# Power_Distro_Board.net
KiCad netlist of a schematic drawn in EAGLE
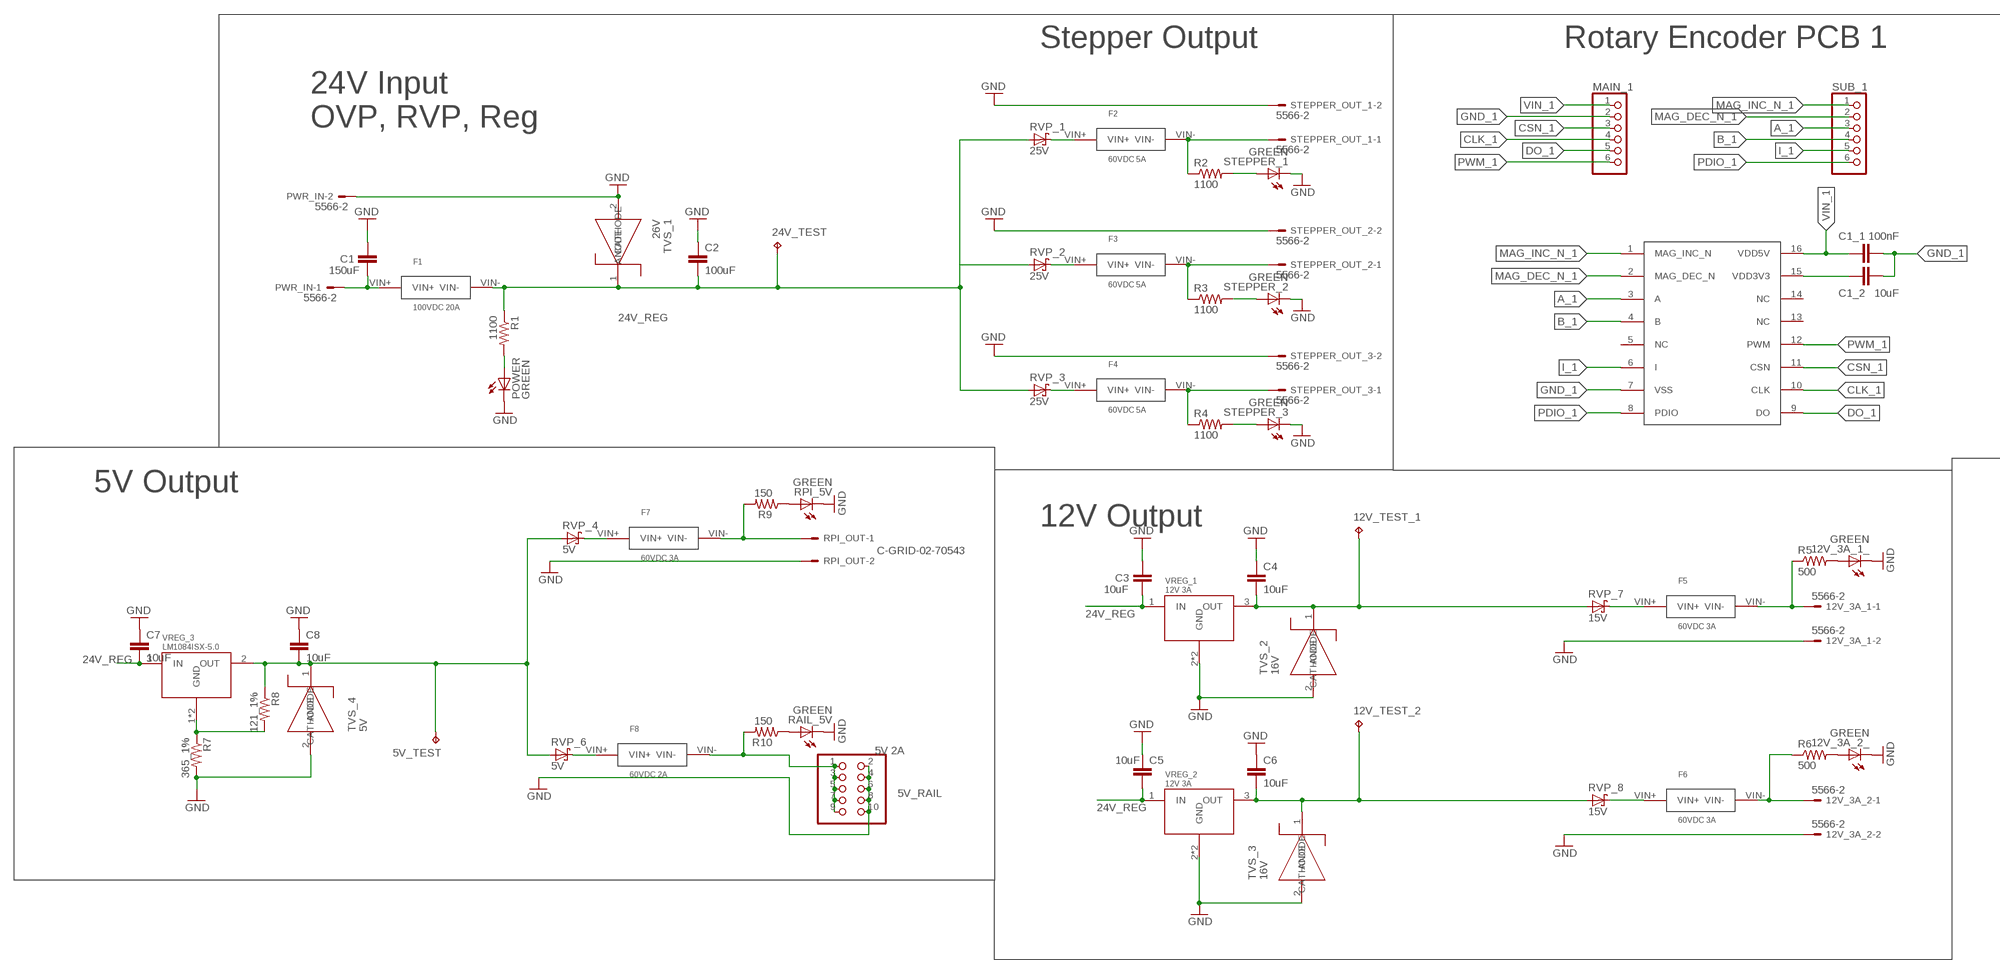
[diagram p0: schematic, sheet 1, part 1 of 2]
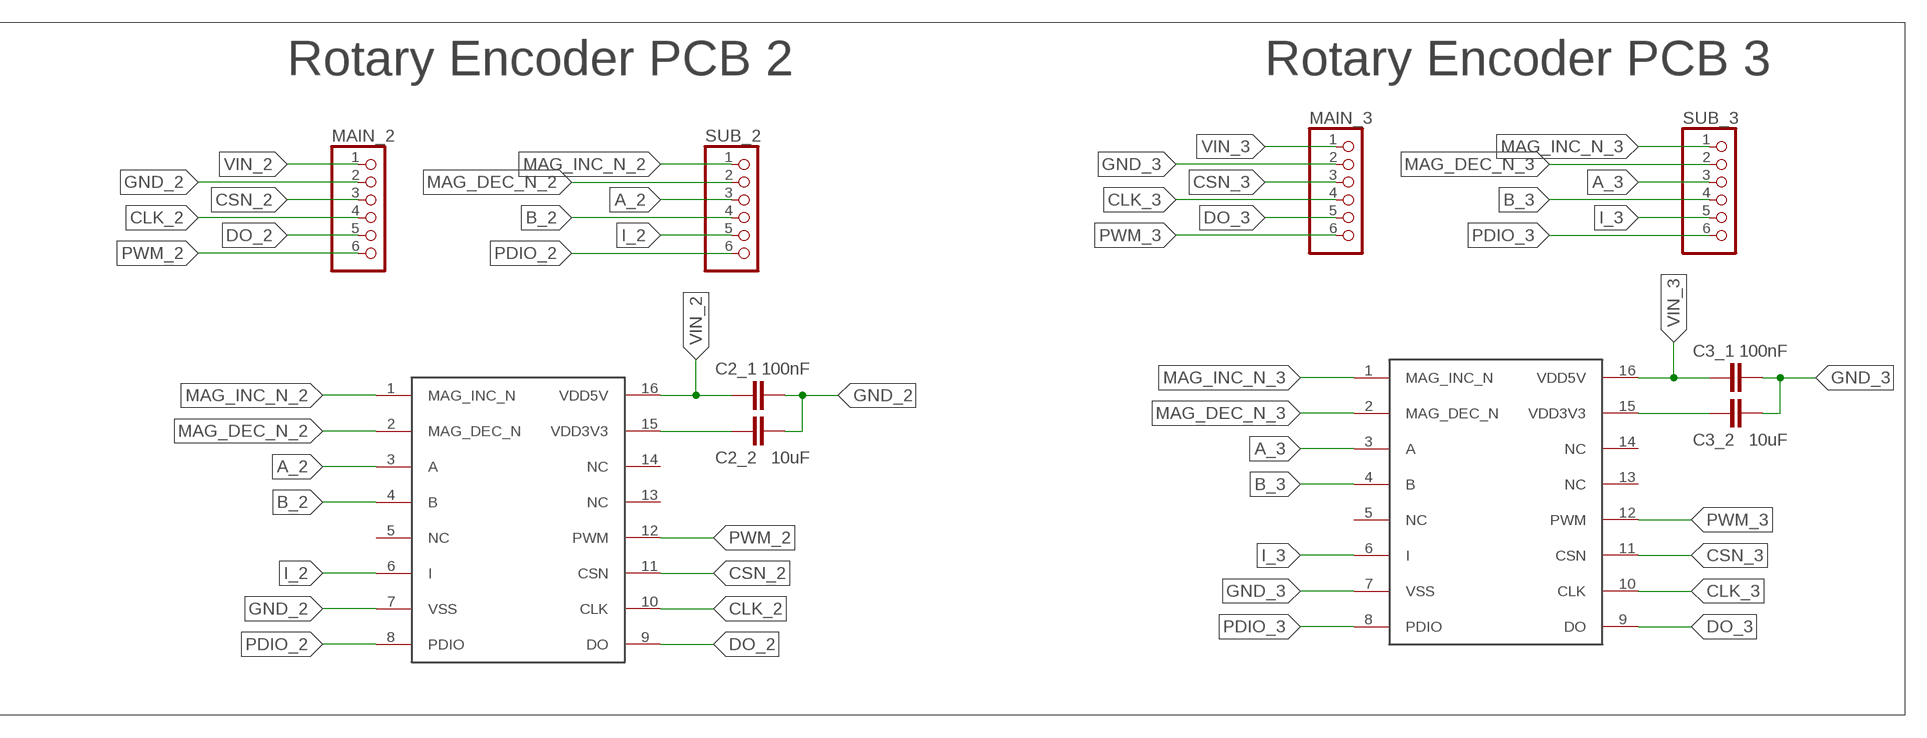
[diagram p1: schematic, sheet 1, part 2 of 2]

(export (version "E")
  (design (tool "Eeschema 10.0.6"))
  (components
    (comp (ref "5V_RAIL")
      (value "5V 2A")
      (footprint "eagle-import:2X05")
      (libsource (lib "eagle-import") (part "PINHD-2X5"))
    )
    (comp (ref "5V_TEST")
      (value "TPPAD1-13")
      (footprint "eagle-import:P1-13")
      (libsource (lib "eagle-import") (part "TPPAD1-13"))
    )
    (comp (ref "12V_3A_1")
      (value "5566-2")
      (footprint "eagle-import:5566-2")
      (libsource (lib "eagle-import") (part "5566-2"))
    )
    (comp (ref "12V_3A_1_")
      (value "GREEN")
      (footprint "eagle-import:SML1206")
      (libsource (lib "eagle-import") (part "LEDSML1206"))
    )
    (comp (ref "12V_3A_2")
      (value "5566-2")
      (footprint "eagle-import:5566-2")
      (libsource (lib "eagle-import") (part "5566-2"))
    )
    (comp (ref "12V_3A_2_")
      (value "GREEN")
      (footprint "eagle-import:SML1206")
      (libsource (lib "eagle-import") (part "LEDSML1206"))
    )
    (comp (ref "12V_TEST_1")
      (value "TPPAD1-13")
      (footprint "eagle-import:P1-13")
      (libsource (lib "eagle-import") (part "TPPAD1-13"))
    )
    (comp (ref "12V_TEST_2")
      (value "TPPAD1-13")
      (footprint "eagle-import:P1-13")
      (libsource (lib "eagle-import") (part "TPPAD1-13"))
    )
    (comp (ref "24V_TEST")
      (value "TPPAD1-13")
      (footprint "eagle-import:P1-13")
      (libsource (lib "eagle-import") (part "TPPAD1-13"))
    )
    (comp (ref "C1")
      (value "150uF")
      (footprint "eagle-import:C1206")
      (libsource (lib "eagle-import") (part "C-EUC1206"))
    )
    (comp (ref "C1_1")
      (value "100nF")
      (footprint "eagle-import:C1206")
      (libsource (lib "eagle-import") (part "C-EUC1206"))
    )
    (comp (ref "C1_2")
      (value "10uF")
      (footprint "eagle-import:C1206")
      (libsource (lib "eagle-import") (part "C-EUC1206"))
    )
    (comp (ref "C2")
      (value "100uF")
      (footprint "eagle-import:C1206")
      (libsource (lib "eagle-import") (part "C-EUC1206"))
    )
    (comp (ref "C2_1")
      (value "100nF")
      (footprint "eagle-import:C1206")
      (libsource (lib "eagle-import") (part "C-EUC1206"))
    )
    (comp (ref "C2_2")
      (value "10uF")
      (footprint "eagle-import:C1206")
      (libsource (lib "eagle-import") (part "C-EUC1206"))
    )
    (comp (ref "C3")
      (value "10uF")
      (footprint "eagle-import:C1206")
      (libsource (lib "eagle-import") (part "C-EUC1206"))
    )
    (comp (ref "C3_1")
      (value "100nF")
      (footprint "eagle-import:C1206")
      (libsource (lib "eagle-import") (part "C-EUC1206"))
    )
    (comp (ref "C3_2")
      (value "10uF")
      (footprint "eagle-import:C1206")
      (libsource (lib "eagle-import") (part "C-EUC1206"))
    )
    (comp (ref "C4")
      (value "10uF")
      (footprint "eagle-import:C1206")
      (libsource (lib "eagle-import") (part "C-EUC1206"))
    )
    (comp (ref "C5")
      (value "10uF")
      (footprint "eagle-import:C1206")
      (libsource (lib "eagle-import") (part "C-EUC1206"))
    )
    (comp (ref "C6")
      (value "10uF")
      (footprint "eagle-import:C1206")
      (libsource (lib "eagle-import") (part "C-EUC1206"))
    )
    (comp (ref "C7")
      (value "10uF")
      (footprint "eagle-import:C1206")
      (libsource (lib "eagle-import") (part "C-EUC1206"))
    )
    (comp (ref "C8")
      (value "10uF")
      (footprint "eagle-import:C1206")
      (libsource (lib "eagle-import") (part "C-EUC1206"))
    )
    (comp (ref "ENC_1")
      (value "ENCODER_AS5045B")
      (footprint "eagle-import:SSOP16")
      (libsource (lib "eagle-import") (part "ENCODER_AS5045B"))
    )
    (comp (ref "ENC_2")
      (value "ENCODER_AS5045B")
      (footprint "eagle-import:SSOP16")
      (libsource (lib "eagle-import") (part "ENCODER_AS5045B"))
    )
    (comp (ref "ENC_3")
      (value "ENCODER_AS5045B")
      (footprint "eagle-import:SSOP16")
      (libsource (lib "eagle-import") (part "ENCODER_AS5045B"))
    )
    (comp (ref "F1")
      (value "100VDC 20A")
      (footprint "eagle-import:NANO")
      (libsource (lib "eagle-import") (part "LITTLEFUSENANO463"))
    )
    (comp (ref "F2")
      (value "60VDC 5A")
      (footprint "eagle-import:OMNI_BLOCK")
      (libsource (lib "eagle-import") (part "LITTLEFUSE0154"))
    )
    (comp (ref "F3")
      (value "60VDC 5A")
      (footprint "eagle-import:OMNI_BLOCK")
      (libsource (lib "eagle-import") (part "LITTLEFUSE0154"))
    )
    (comp (ref "F4")
      (value "60VDC 5A")
      (footprint "eagle-import:OMNI_BLOCK")
      (libsource (lib "eagle-import") (part "LITTLEFUSE0154"))
    )
    (comp (ref "F5")
      (value "60VDC 3A")
      (footprint "eagle-import:OMNI_BLOCK")
      (libsource (lib "eagle-import") (part "LITTLEFUSE0154"))
    )
    (comp (ref "F6")
      (value "60VDC 3A")
      (footprint "eagle-import:OMNI_BLOCK")
      (libsource (lib "eagle-import") (part "LITTLEFUSE0154"))
    )
    (comp (ref "F7")
      (value "60VDC 3A")
      (footprint "eagle-import:OMNI_BLOCK")
      (libsource (lib "eagle-import") (part "LITTLEFUSE0154"))
    )
    (comp (ref "F8")
      (value "60VDC 2A")
      (footprint "eagle-import:OMNI_BLOCK")
      (libsource (lib "eagle-import") (part "LITTLEFUSE0154"))
    )
    (comp (ref "MAIN_1")
      (value "PINHD-1X6")
      (footprint "eagle-import:1X06")
      (libsource (lib "eagle-import") (part "PINHD-1X6"))
    )
    (comp (ref "MAIN_2")
      (value "PINHD-1X6")
      (footprint "eagle-import:1X06")
      (libsource (lib "eagle-import") (part "PINHD-1X6"))
    )
    (comp (ref "MAIN_3")
      (value "PINHD-1X6")
      (footprint "eagle-import:1X06")
      (libsource (lib "eagle-import") (part "PINHD-1X6"))
    )
    (comp (ref "POWER")
      (value "GREEN")
      (footprint "eagle-import:SML1206")
      (libsource (lib "eagle-import") (part "LEDSML1206"))
    )
    (comp (ref "PWR_IN")
      (value "5566-2")
      (footprint "eagle-import:5566-2")
      (libsource (lib "eagle-import") (part "5566-2"))
    )
    (comp (ref "R1")
      (value "1100")
      (footprint "eagle-import:R1206")
      (libsource (lib "eagle-import") (part "R-US_R1206"))
    )
    (comp (ref "R2")
      (value "1100")
      (footprint "eagle-import:R1206")
      (libsource (lib "eagle-import") (part "R-US_R1206"))
    )
    (comp (ref "R3")
      (value "1100")
      (footprint "eagle-import:R1206")
      (libsource (lib "eagle-import") (part "R-US_R1206"))
    )
    (comp (ref "R4")
      (value "1100")
      (footprint "eagle-import:R1206")
      (libsource (lib "eagle-import") (part "R-US_R1206"))
    )
    (comp (ref "R5")
      (value "500")
      (footprint "eagle-import:R1206")
      (libsource (lib "eagle-import") (part "R-US_R1206"))
    )
    (comp (ref "R6")
      (value "500")
      (footprint "eagle-import:R1206")
      (libsource (lib "eagle-import") (part "R-US_R1206"))
    )
    (comp (ref "R7")
      (value "365_1%")
      (footprint "eagle-import:R1206")
      (libsource (lib "eagle-import") (part "R-US_R1206"))
    )
    (comp (ref "R8")
      (value "121_1%")
      (footprint "eagle-import:R1206")
      (libsource (lib "eagle-import") (part "R-US_R1206"))
    )
    (comp (ref "R9")
      (value "150")
      (footprint "eagle-import:R1206")
      (libsource (lib "eagle-import") (part "R-US_R1206"))
    )
    (comp (ref "R10")
      (value "150")
      (footprint "eagle-import:R1206")
      (libsource (lib "eagle-import") (part "R-US_R1206"))
    )
    (comp (ref "RAIL_5V")
      (value "GREEN")
      (footprint "eagle-import:SML1206")
      (libsource (lib "eagle-import") (part "LEDSML1206"))
    )
    (comp (ref "RPI_5V")
      (value "GREEN")
      (footprint "eagle-import:SML1206")
      (libsource (lib "eagle-import") (part "LEDSML1206"))
    )
    (comp (ref "RPI_OUT")
      (value "C-GRID-02-70543")
      (footprint "eagle-import:70543-02")
      (libsource (lib "eagle-import") (part "C-GRID-02-70543"))
    )
    (comp (ref "RVP_1")
      (value "25V")
      (footprint "eagle-import:SMC")
      (libsource (lib "eagle-import") (part "SCHOTTKY-DIODESMC"))
    )
    (comp (ref "RVP_2")
      (value "25V")
      (footprint "eagle-import:SMC")
      (libsource (lib "eagle-import") (part "SCHOTTKY-DIODESMC"))
    )
    (comp (ref "RVP_3")
      (value "25V")
      (footprint "eagle-import:SMC")
      (libsource (lib "eagle-import") (part "SCHOTTKY-DIODESMC"))
    )
    (comp (ref "RVP_4")
      (value "5V")
      (footprint "eagle-import:SMC")
      (libsource (lib "eagle-import") (part "SCHOTTKY-DIODESMC"))
    )
    (comp (ref "RVP_6")
      (value "5V")
      (footprint "eagle-import:SMC")
      (libsource (lib "eagle-import") (part "SCHOTTKY-DIODESMC"))
    )
    (comp (ref "RVP_7")
      (value "15V")
      (footprint "eagle-import:SMC")
      (libsource (lib "eagle-import") (part "SCHOTTKY-DIODESMC"))
    )
    (comp (ref "RVP_8")
      (value "15V")
      (footprint "eagle-import:SMC")
      (libsource (lib "eagle-import") (part "SCHOTTKY-DIODESMC"))
    )
    (comp (ref "STEPPER_1")
      (value "GREEN")
      (footprint "eagle-import:SML1206")
      (libsource (lib "eagle-import") (part "LEDSML1206"))
    )
    (comp (ref "STEPPER_2")
      (value "GREEN")
      (footprint "eagle-import:SML1206")
      (libsource (lib "eagle-import") (part "LEDSML1206"))
    )
    (comp (ref "STEPPER_3")
      (value "GREEN")
      (footprint "eagle-import:SML1206")
      (libsource (lib "eagle-import") (part "LEDSML1206"))
    )
    (comp (ref "STEPPER_OUT_1")
      (value "5566-2")
      (footprint "eagle-import:5566-2")
      (libsource (lib "eagle-import") (part "5566-2"))
    )
    (comp (ref "STEPPER_OUT_2")
      (value "5566-2")
      (footprint "eagle-import:5566-2")
      (libsource (lib "eagle-import") (part "5566-2"))
    )
    (comp (ref "STEPPER_OUT_3")
      (value "5566-2")
      (footprint "eagle-import:5566-2")
      (libsource (lib "eagle-import") (part "5566-2"))
    )
    (comp (ref "SUB_1")
      (value "PINHD-1X6")
      (footprint "eagle-import:1X06")
      (libsource (lib "eagle-import") (part "PINHD-1X6"))
    )
    (comp (ref "SUB_2")
      (value "PINHD-1X6")
      (footprint "eagle-import:1X06")
      (libsource (lib "eagle-import") (part "PINHD-1X6"))
    )
    (comp (ref "SUB_3")
      (value "PINHD-1X6")
      (footprint "eagle-import:1X06")
      (libsource (lib "eagle-import") (part "PINHD-1X6"))
    )
    (comp (ref "TVS_1")
      (value "26V")
      (footprint "eagle-import:DO-214AC")
      (libsource (lib "eagle-import") (part "SMAJ26A_TVSSMA"))
    )
    (comp (ref "TVS_2")
      (value "16V")
      (footprint "eagle-import:DO-214AC")
      (libsource (lib "eagle-import") (part "PRSMA16_TVS"))
    )
    (comp (ref "TVS_3")
      (value "16V")
      (footprint "eagle-import:DO-214AC")
      (libsource (lib "eagle-import") (part "PRSMA16_TVS"))
    )
    (comp (ref "TVS_4")
      (value "5V")
      (footprint "eagle-import:DO-214AC")
      (libsource (lib "eagle-import") (part "SMAJ5.0_TVSSMA"))
    )
    (comp (ref "VREG_1")
      (value "12V 3A")
      (footprint "eagle-import:TO-263-3")
      (libsource (lib "eagle-import") (part "MIC29300-12WUSMA"))
    )
    (comp (ref "VREG_2")
      (value "12V 3A")
      (footprint "eagle-import:TO-263-3")
      (libsource (lib "eagle-import") (part "MIC29300-12WUSMA"))
    )
    (comp (ref "VREG_3")
      (value "LM1084ISX-5.0")
      (footprint "eagle-import:TO-263-3")
      (libsource (lib "eagle-import") (part "LM1084ISX-5.0"))
    )
  )
  (nets
    (net (code "1") (name "/24V_REG") (class "Default")
      (node (ref "24V_TEST") (pin "TP") (pinfunction "TP_TP") (pintype "input"))
      (node (ref "C2") (pin "2") (pinfunction "2_2") (pintype "passive"))
      (node (ref "C3") (pin "2") (pinfunction "2_2") (pintype "passive"))
      (node (ref "C5") (pin "2") (pinfunction "2_2") (pintype "passive"))
      (node (ref "C7") (pin "2") (pinfunction "2_2") (pintype "passive"))
      (node (ref "F1") (pin "VIN-") (pinfunction "VIN-_VIN-") (pintype "bidirectional"))
      (node (ref "R1") (pin "1") (pinfunction "1_1") (pintype "passive"))
      (node (ref "RVP_1") (pin "A") (pinfunction "A_A") (pintype "passive"))
      (node (ref "RVP_2") (pin "A") (pinfunction "A_A") (pintype "passive"))
      (node (ref "RVP_3") (pin "A") (pinfunction "A_A") (pintype "passive"))
      (node (ref "TVS_1") (pin "1") (pinfunction "CATHODE_1") (pintype "bidirectional"))
      (node (ref "VREG_1") (pin "1") (pinfunction "IN_1") (pintype "bidirectional"))
      (node (ref "VREG_2") (pin "1") (pinfunction "IN_1") (pintype "bidirectional"))
      (node (ref "VREG_3") (pin "3") (pinfunction "IN_3") (pintype "bidirectional"))
    )
    (net (code "2") (name "A_1") (class "Default")
      (node (ref "ENC_1") (pin "3") (pinfunction "A_3") (pintype "bidirectional"))
      (node (ref "SUB_1") (pin "3") (pinfunction "3_3") (pintype "passive"))
    )
    (net (code "3") (name "A_2") (class "Default")
      (node (ref "ENC_2") (pin "3") (pinfunction "A_3") (pintype "bidirectional"))
      (node (ref "SUB_2") (pin "3") (pinfunction "3_3") (pintype "passive"))
    )
    (net (code "4") (name "A_3") (class "Default")
      (node (ref "ENC_3") (pin "3") (pinfunction "A_3") (pintype "bidirectional"))
      (node (ref "SUB_3") (pin "3") (pinfunction "3_3") (pintype "passive"))
    )
    (net (code "5") (name "B_1") (class "Default")
      (node (ref "ENC_1") (pin "4") (pinfunction "B_4") (pintype "bidirectional"))
      (node (ref "SUB_1") (pin "4") (pinfunction "4_4") (pintype "passive"))
    )
    (net (code "6") (name "B_2") (class "Default")
      (node (ref "ENC_2") (pin "4") (pinfunction "B_4") (pintype "bidirectional"))
      (node (ref "SUB_2") (pin "4") (pinfunction "4_4") (pintype "passive"))
    )
    (net (code "7") (name "B_3") (class "Default")
      (node (ref "ENC_3") (pin "4") (pinfunction "B_4") (pintype "bidirectional"))
      (node (ref "SUB_3") (pin "4") (pinfunction "4_4") (pintype "passive"))
    )
    (net (code "8") (name "CLK_1") (class "Default")
      (node (ref "ENC_1") (pin "10") (pinfunction "CLK_10") (pintype "bidirectional"))
      (node (ref "MAIN_1") (pin "4") (pinfunction "4_4") (pintype "passive"))
    )
    (net (code "9") (name "CLK_2") (class "Default")
      (node (ref "ENC_2") (pin "10") (pinfunction "CLK_10") (pintype "bidirectional"))
      (node (ref "MAIN_2") (pin "4") (pinfunction "4_4") (pintype "passive"))
    )
    (net (code "10") (name "CLK_3") (class "Default")
      (node (ref "ENC_3") (pin "10") (pinfunction "CLK_10") (pintype "bidirectional"))
      (node (ref "MAIN_3") (pin "4") (pinfunction "4_4") (pintype "passive"))
    )
    (net (code "11") (name "CSN_1") (class "Default")
      (node (ref "ENC_1") (pin "11") (pinfunction "CSN_11") (pintype "bidirectional"))
      (node (ref "MAIN_1") (pin "3") (pinfunction "3_3") (pintype "passive"))
    )
    (net (code "12") (name "CSN_2") (class "Default")
      (node (ref "ENC_2") (pin "11") (pinfunction "CSN_11") (pintype "bidirectional"))
      (node (ref "MAIN_2") (pin "3") (pinfunction "3_3") (pintype "passive"))
    )
    (net (code "13") (name "CSN_3") (class "Default")
      (node (ref "ENC_3") (pin "11") (pinfunction "CSN_11") (pintype "bidirectional"))
      (node (ref "MAIN_3") (pin "3") (pinfunction "3_3") (pintype "passive"))
    )
    (net (code "14") (name "DO_1") (class "Default")
      (node (ref "ENC_1") (pin "9") (pinfunction "DO_9") (pintype "bidirectional"))
      (node (ref "MAIN_1") (pin "5") (pinfunction "5_5") (pintype "passive"))
    )
    (net (code "15") (name "DO_2") (class "Default")
      (node (ref "ENC_2") (pin "9") (pinfunction "DO_9") (pintype "bidirectional"))
      (node (ref "MAIN_2") (pin "5") (pinfunction "5_5") (pintype "passive"))
    )
    (net (code "16") (name "DO_3") (class "Default")
      (node (ref "ENC_3") (pin "9") (pinfunction "DO_9") (pintype "bidirectional"))
      (node (ref "MAIN_3") (pin "5") (pinfunction "5_5") (pintype "passive"))
    )
    (net (code "17") (name "GND") (class "Default")
      (node (ref "12V_3A_1") (pin "2") (pinfunction "S_2") (pintype "passive"))
      (node (ref "12V_3A_1_") (pin "C") (pinfunction "C_C") (pintype "passive"))
      (node (ref "12V_3A_2") (pin "2") (pinfunction "S_2") (pintype "passive"))
      (node (ref "12V_3A_2_") (pin "C") (pinfunction "C_C") (pintype "passive"))
      (node (ref "5V_RAIL") (pin "10") (pinfunction "10_10") (pintype "passive"))
      (node (ref "5V_RAIL") (pin "2") (pinfunction "2_2") (pintype "passive"))
      (node (ref "5V_RAIL") (pin "4") (pinfunction "4_4") (pintype "passive"))
      (node (ref "5V_RAIL") (pin "6") (pinfunction "6_6") (pintype "passive"))
      (node (ref "5V_RAIL") (pin "8") (pinfunction "8_8") (pintype "passive"))
      (node (ref "C1") (pin "1") (pinfunction "1_1") (pintype "passive"))
      (node (ref "C2") (pin "1") (pinfunction "1_1") (pintype "passive"))
      (node (ref "C3") (pin "1") (pinfunction "1_1") (pintype "passive"))
      (node (ref "C4") (pin "1") (pinfunction "1_1") (pintype "passive"))
      (node (ref "C5") (pin "1") (pinfunction "1_1") (pintype "passive"))
      (node (ref "C6") (pin "1") (pinfunction "1_1") (pintype "passive"))
      (node (ref "C7") (pin "1") (pinfunction "1_1") (pintype "passive"))
      (node (ref "C8") (pin "1") (pinfunction "1_1") (pintype "passive"))
      (node (ref "POWER") (pin "C") (pinfunction "C_C") (pintype "passive"))
      (node (ref "PWR_IN") (pin "2") (pinfunction "S_2") (pintype "passive"))
      (node (ref "R7") (pin "2") (pinfunction "2_2") (pintype "passive"))
      (node (ref "RAIL_5V") (pin "C") (pinfunction "C_C") (pintype "passive"))
      (node (ref "RPI_5V") (pin "C") (pinfunction "C_C") (pintype "passive"))
      (node (ref "RPI_OUT") (pin "2") (pinfunction "S_2") (pintype "passive"))
      (node (ref "STEPPER_1") (pin "C") (pinfunction "C_C") (pintype "passive"))
      (node (ref "STEPPER_2") (pin "C") (pinfunction "C_C") (pintype "passive"))
      (node (ref "STEPPER_3") (pin "C") (pinfunction "C_C") (pintype "passive"))
      (node (ref "STEPPER_OUT_1") (pin "2") (pinfunction "S_2") (pintype "passive"))
      (node (ref "STEPPER_OUT_2") (pin "2") (pinfunction "S_2") (pintype "passive"))
      (node (ref "STEPPER_OUT_3") (pin "2") (pinfunction "S_2") (pintype "passive"))
      (node (ref "TVS_1") (pin "2") (pinfunction "ANODE_2") (pintype "bidirectional"))
      (node (ref "TVS_2") (pin "2") (pinfunction "ANODE_2") (pintype "bidirectional"))
      (node (ref "TVS_3") (pin "2") (pinfunction "ANODE_2") (pintype "bidirectional"))
      (node (ref "TVS_4") (pin "2") (pinfunction "ANODE_2") (pintype "bidirectional"))
      (node (ref "VREG_1") (pin "2") (pinfunction "GND_2") (pintype "bidirectional"))
      (node (ref "VREG_1") (pin "4") (pinfunction "GND_4") (pintype "bidirectional"))
      (node (ref "VREG_2") (pin "2") (pinfunction "GND_2") (pintype "bidirectional"))
      (node (ref "VREG_2") (pin "4") (pinfunction "GND_4") (pintype "bidirectional"))
    )
    (net (code "18") (name "GND_1") (class "Default")
      (node (ref "C1_1") (pin "2") (pinfunction "2_2") (pintype "passive"))
      (node (ref "C1_2") (pin "2") (pinfunction "2_2") (pintype "passive"))
      (node (ref "ENC_1") (pin "7") (pinfunction "VSS_7") (pintype "bidirectional"))
      (node (ref "MAIN_1") (pin "2") (pinfunction "2_2") (pintype "passive"))
    )
    (net (code "19") (name "GND_2") (class "Default")
      (node (ref "C2_1") (pin "2") (pinfunction "2_2") (pintype "passive"))
      (node (ref "C2_2") (pin "2") (pinfunction "2_2") (pintype "passive"))
      (node (ref "ENC_2") (pin "7") (pinfunction "VSS_7") (pintype "bidirectional"))
      (node (ref "MAIN_2") (pin "2") (pinfunction "2_2") (pintype "passive"))
    )
    (net (code "20") (name "GND_3") (class "Default")
      (node (ref "C3_1") (pin "2") (pinfunction "2_2") (pintype "passive"))
      (node (ref "C3_2") (pin "2") (pinfunction "2_2") (pintype "passive"))
      (node (ref "ENC_3") (pin "7") (pinfunction "VSS_7") (pintype "bidirectional"))
      (node (ref "MAIN_3") (pin "2") (pinfunction "2_2") (pintype "passive"))
    )
    (net (code "21") (name "I_1") (class "Default")
      (node (ref "ENC_1") (pin "6") (pinfunction "I_6") (pintype "bidirectional"))
      (node (ref "SUB_1") (pin "5") (pinfunction "5_5") (pintype "passive"))
    )
    (net (code "22") (name "I_2") (class "Default")
      (node (ref "ENC_2") (pin "6") (pinfunction "I_6") (pintype "bidirectional"))
      (node (ref "SUB_2") (pin "5") (pinfunction "5_5") (pintype "passive"))
    )
    (net (code "23") (name "I_3") (class "Default")
      (node (ref "ENC_3") (pin "6") (pinfunction "I_6") (pintype "bidirectional"))
      (node (ref "SUB_3") (pin "5") (pinfunction "5_5") (pintype "passive"))
    )
    (net (code "24") (name "MAG_DEC_N_1") (class "Default")
      (node (ref "ENC_1") (pin "2") (pinfunction "MAG_DEC_N_2") (pintype "bidirectional"))
      (node (ref "SUB_1") (pin "2") (pinfunction "2_2") (pintype "passive"))
    )
    (net (code "25") (name "MAG_DEC_N_2") (class "Default")
      (node (ref "ENC_2") (pin "2") (pinfunction "MAG_DEC_N_2") (pintype "bidirectional"))
      (node (ref "SUB_2") (pin "2") (pinfunction "2_2") (pintype "passive"))
    )
    (net (code "26") (name "MAG_DEC_N_3") (class "Default")
      (node (ref "ENC_3") (pin "2") (pinfunction "MAG_DEC_N_2") (pintype "bidirectional"))
      (node (ref "SUB_3") (pin "2") (pinfunction "2_2") (pintype "passive"))
    )
    (net (code "27") (name "MAG_INC_N_1") (class "Default")
      (node (ref "ENC_1") (pin "1") (pinfunction "MAG_INC_N_1") (pintype "bidirectional"))
      (node (ref "SUB_1") (pin "1") (pinfunction "1_1") (pintype "passive"))
    )
    (net (code "28") (name "MAG_INC_N_2") (class "Default")
      (node (ref "ENC_2") (pin "1") (pinfunction "MAG_INC_N_1") (pintype "bidirectional"))
      (node (ref "SUB_2") (pin "1") (pinfunction "1_1") (pintype "passive"))
    )
    (net (code "29") (name "MAG_INC_N_3") (class "Default")
      (node (ref "ENC_3") (pin "1") (pinfunction "MAG_INC_N_1") (pintype "bidirectional"))
      (node (ref "SUB_3") (pin "1") (pinfunction "1_1") (pintype "passive"))
    )
    (net (code "30") (name "Net-(5V_RAIL-Pad1)") (class "Default")
      (node (ref "5V_RAIL") (pin "1") (pinfunction "1_1") (pintype "passive"))
      (node (ref "5V_RAIL") (pin "3") (pinfunction "3_3") (pintype "passive"))
      (node (ref "5V_RAIL") (pin "5") (pinfunction "5_5") (pintype "passive"))
      (node (ref "5V_RAIL") (pin "7") (pinfunction "7_7") (pintype "passive"))
      (node (ref "5V_RAIL") (pin "9") (pinfunction "9_9") (pintype "passive"))
      (node (ref "F8") (pin "VIN-") (pinfunction "VIN-_VIN-") (pintype "bidirectional"))
      (node (ref "R10") (pin "2") (pinfunction "2_2") (pintype "passive"))
    )
    (net (code "31") (name "Net-(12V_3A_1A-S)") (class "Default")
      (node (ref "12V_3A_1") (pin "1") (pinfunction "S_1") (pintype "passive"))
      (node (ref "F5") (pin "VIN-") (pinfunction "VIN-_VIN-") (pintype "bidirectional"))
      (node (ref "R5") (pin "1") (pinfunction "1_1") (pintype "passive"))
    )
    (net (code "32") (name "Net-(12V_3A_1_-PadA)") (class "Default")
      (node (ref "12V_3A_1_") (pin "A") (pinfunction "A_A") (pintype "passive"))
      (node (ref "R5") (pin "2") (pinfunction "2_2") (pintype "passive"))
    )
    (net (code "33") (name "Net-(12V_3A_2A-S)") (class "Default")
      (node (ref "12V_3A_2") (pin "1") (pinfunction "S_1") (pintype "passive"))
      (node (ref "F6") (pin "VIN-") (pinfunction "VIN-_VIN-") (pintype "bidirectional"))
      (node (ref "R6") (pin "1") (pinfunction "1_1") (pintype "passive"))
    )
    (net (code "34") (name "Net-(12V_3A_2_-PadA)") (class "Default")
      (node (ref "12V_3A_2_") (pin "A") (pinfunction "A_A") (pintype "passive"))
      (node (ref "R6") (pin "2") (pinfunction "2_2") (pintype "passive"))
    )
    (net (code "35") (name "Net-(ENC_1-VDD3V3)") (class "Default")
      (node (ref "C1_2") (pin "1") (pinfunction "1_1") (pintype "passive"))
      (node (ref "ENC_1") (pin "15") (pinfunction "VDD3V3_15") (pintype "bidirectional"))
    )
    (net (code "36") (name "Net-(ENC_2-VDD3V3)") (class "Default")
      (node (ref "C2_2") (pin "1") (pinfunction "1_1") (pintype "passive"))
      (node (ref "ENC_2") (pin "15") (pinfunction "VDD3V3_15") (pintype "bidirectional"))
    )
    (net (code "37") (name "Net-(ENC_3-VDD3V3)") (class "Default")
      (node (ref "C3_2") (pin "1") (pinfunction "1_1") (pintype "passive"))
      (node (ref "ENC_3") (pin "15") (pinfunction "VDD3V3_15") (pintype "bidirectional"))
    )
    (net (code "38") (name "Net-(F2-PadVIN+)") (class "Default")
      (node (ref "F2") (pin "VIN+") (pinfunction "VIN+_VIN+") (pintype "bidirectional"))
      (node (ref "RVP_1") (pin "C") (pinfunction "C_C") (pintype "passive"))
    )
    (net (code "39") (name "Net-(F3-PadVIN+)") (class "Default")
      (node (ref "F3") (pin "VIN+") (pinfunction "VIN+_VIN+") (pintype "bidirectional"))
      (node (ref "RVP_2") (pin "C") (pinfunction "C_C") (pintype "passive"))
    )
    (net (code "40") (name "Net-(F4-PadVIN+)") (class "Default")
      (node (ref "F4") (pin "VIN+") (pinfunction "VIN+_VIN+") (pintype "bidirectional"))
      (node (ref "RVP_3") (pin "C") (pinfunction "C_C") (pintype "passive"))
    )
    (net (code "41") (name "Net-(F5-PadVIN+)") (class "Default")
      (node (ref "F5") (pin "VIN+") (pinfunction "VIN+_VIN+") (pintype "bidirectional"))
      (node (ref "RVP_7") (pin "C") (pinfunction "C_C") (pintype "passive"))
    )
    (net (code "42") (name "Net-(F6-PadVIN+)") (class "Default")
      (node (ref "F6") (pin "VIN+") (pinfunction "VIN+_VIN+") (pintype "bidirectional"))
      (node (ref "RVP_8") (pin "C") (pinfunction "C_C") (pintype "passive"))
    )
    (net (code "43") (name "Net-(F7-PadVIN+)") (class "Default")
      (node (ref "F7") (pin "VIN+") (pinfunction "VIN+_VIN+") (pintype "bidirectional"))
      (node (ref "RVP_4") (pin "C") (pinfunction "C_C") (pintype "passive"))
    )
    (net (code "44") (name "Net-(F8-PadVIN+)") (class "Default")
      (node (ref "F8") (pin "VIN+") (pinfunction "VIN+_VIN+") (pintype "bidirectional"))
      (node (ref "RVP_6") (pin "C") (pinfunction "C_C") (pintype "passive"))
    )
    (net (code "45") (name "Net-(POWER-PadA)") (class "Default")
      (node (ref "POWER") (pin "A") (pinfunction "A_A") (pintype "passive"))
      (node (ref "R1") (pin "2") (pinfunction "2_2") (pintype "passive"))
    )
    (net (code "46") (name "Net-(PWR_INA-S)") (class "Default")
      (node (ref "C1") (pin "2") (pinfunction "2_2") (pintype "passive"))
      (node (ref "F1") (pin "VIN+") (pinfunction "VIN+_VIN+") (pintype "bidirectional"))
      (node (ref "PWR_IN") (pin "1") (pinfunction "S_1") (pintype "passive"))
    )
    (net (code "47") (name "Net-(R2-Pad2)") (class "Default")
      (node (ref "R2") (pin "2") (pinfunction "2_2") (pintype "passive"))
      (node (ref "STEPPER_1") (pin "A") (pinfunction "A_A") (pintype "passive"))
    )
    (net (code "48") (name "Net-(R3-Pad2)") (class "Default")
      (node (ref "R3") (pin "2") (pinfunction "2_2") (pintype "passive"))
      (node (ref "STEPPER_2") (pin "A") (pinfunction "A_A") (pintype "passive"))
    )
    (net (code "49") (name "Net-(R4-Pad2)") (class "Default")
      (node (ref "R4") (pin "2") (pinfunction "2_2") (pintype "passive"))
      (node (ref "STEPPER_3") (pin "A") (pinfunction "A_A") (pintype "passive"))
    )
    (net (code "50") (name "Net-(R7-Pad1)") (class "Default")
      (node (ref "R7") (pin "1") (pinfunction "1_1") (pintype "passive"))
      (node (ref "R8") (pin "2") (pinfunction "2_2") (pintype "passive"))
      (node (ref "VREG_3") (pin "1") (pinfunction "GND_1") (pintype "bidirectional"))
      (node (ref "VREG_3") (pin "4") (pinfunction "GND_4") (pintype "bidirectional"))
    )
    (net (code "51") (name "Net-(R9-Pad1)") (class "Default")
      (node (ref "R9") (pin "1") (pinfunction "1_1") (pintype "passive"))
      (node (ref "RPI_5V") (pin "A") (pinfunction "A_A") (pintype "passive"))
    )
    (net (code "52") (name "Net-(R10-Pad1)") (class "Default")
      (node (ref "R10") (pin "1") (pinfunction "1_1") (pintype "passive"))
      (node (ref "RAIL_5V") (pin "A") (pinfunction "A_A") (pintype "passive"))
    )
    (net (code "53") (name "Net-(RPI_OUTA-S)") (class "Default")
      (node (ref "F7") (pin "VIN-") (pinfunction "VIN-_VIN-") (pintype "bidirectional"))
      (node (ref "R9") (pin "2") (pinfunction "2_2") (pintype "passive"))
      (node (ref "RPI_OUT") (pin "1") (pinfunction "S_1") (pintype "passive"))
    )
    (net (code "54") (name "Net-(STEPPER_OUT_1A-S)") (class "Default")
      (node (ref "F2") (pin "VIN-") (pinfunction "VIN-_VIN-") (pintype "bidirectional"))
      (node (ref "R2") (pin "1") (pinfunction "1_1") (pintype "passive"))
      (node (ref "STEPPER_OUT_1") (pin "1") (pinfunction "S_1") (pintype "passive"))
    )
    (net (code "55") (name "Net-(STEPPER_OUT_2A-S)") (class "Default")
      (node (ref "F3") (pin "VIN-") (pinfunction "VIN-_VIN-") (pintype "bidirectional"))
      (node (ref "R3") (pin "1") (pinfunction "1_1") (pintype "passive"))
      (node (ref "STEPPER_OUT_2") (pin "1") (pinfunction "S_1") (pintype "passive"))
    )
    (net (code "56") (name "Net-(STEPPER_OUT_3A-S)") (class "Default")
      (node (ref "F4") (pin "VIN-") (pinfunction "VIN-_VIN-") (pintype "bidirectional"))
      (node (ref "R4") (pin "1") (pinfunction "1_1") (pintype "passive"))
      (node (ref "STEPPER_OUT_3") (pin "1") (pinfunction "S_1") (pintype "passive"))
    )
    (net (code "57") (name "Net-(TVS_2-CATHODE)") (class "Default")
      (node (ref "12V_TEST_1") (pin "TP") (pinfunction "TP_TP") (pintype "input"))
      (node (ref "C4") (pin "2") (pinfunction "2_2") (pintype "passive"))
      (node (ref "RVP_7") (pin "A") (pinfunction "A_A") (pintype "passive"))
      (node (ref "TVS_2") (pin "1") (pinfunction "CATHODE_1") (pintype "bidirectional"))
      (node (ref "VREG_1") (pin "3") (pinfunction "OUT_3") (pintype "bidirectional"))
    )
    (net (code "58") (name "Net-(TVS_3-CATHODE)") (class "Default")
      (node (ref "12V_TEST_2") (pin "TP") (pinfunction "TP_TP") (pintype "input"))
      (node (ref "C6") (pin "2") (pinfunction "2_2") (pintype "passive"))
      (node (ref "RVP_8") (pin "A") (pinfunction "A_A") (pintype "passive"))
      (node (ref "TVS_3") (pin "1") (pinfunction "CATHODE_1") (pintype "bidirectional"))
      (node (ref "VREG_2") (pin "3") (pinfunction "OUT_3") (pintype "bidirectional"))
    )
    (net (code "59") (name "Net-(TVS_4-CATHODE)") (class "Default")
      (node (ref "5V_TEST") (pin "TP") (pinfunction "TP_TP") (pintype "input"))
      (node (ref "C8") (pin "2") (pinfunction "2_2") (pintype "passive"))
      (node (ref "R8") (pin "1") (pinfunction "1_1") (pintype "passive"))
      (node (ref "RVP_4") (pin "A") (pinfunction "A_A") (pintype "passive"))
      (node (ref "RVP_6") (pin "A") (pinfunction "A_A") (pintype "passive"))
      (node (ref "TVS_4") (pin "1") (pinfunction "CATHODE_1") (pintype "bidirectional"))
      (node (ref "VREG_3") (pin "2") (pinfunction "OUT_2") (pintype "bidirectional"))
    )
    (net (code "60") (name "PDIO_1") (class "Default")
      (node (ref "ENC_1") (pin "8") (pinfunction "PDIO_8") (pintype "bidirectional"))
      (node (ref "SUB_1") (pin "6") (pinfunction "6_6") (pintype "passive"))
    )
    (net (code "61") (name "PDIO_2") (class "Default")
      (node (ref "ENC_2") (pin "8") (pinfunction "PDIO_8") (pintype "bidirectional"))
      (node (ref "SUB_2") (pin "6") (pinfunction "6_6") (pintype "passive"))
    )
    (net (code "62") (name "PDIO_3") (class "Default")
      (node (ref "ENC_3") (pin "8") (pinfunction "PDIO_8") (pintype "bidirectional"))
      (node (ref "SUB_3") (pin "6") (pinfunction "6_6") (pintype "passive"))
    )
    (net (code "63") (name "PWM_1") (class "Default")
      (node (ref "ENC_1") (pin "12") (pinfunction "PWM_12") (pintype "bidirectional"))
      (node (ref "MAIN_1") (pin "6") (pinfunction "6_6") (pintype "passive"))
    )
    (net (code "64") (name "PWM_2") (class "Default")
      (node (ref "ENC_2") (pin "12") (pinfunction "PWM_12") (pintype "bidirectional"))
      (node (ref "MAIN_2") (pin "6") (pinfunction "6_6") (pintype "passive"))
    )
    (net (code "65") (name "PWM_3") (class "Default")
      (node (ref "ENC_3") (pin "12") (pinfunction "PWM_12") (pintype "bidirectional"))
      (node (ref "MAIN_3") (pin "6") (pinfunction "6_6") (pintype "passive"))
    )
    (net (code "66") (name "VIN_1") (class "Default")
      (node (ref "C1_1") (pin "1") (pinfunction "1_1") (pintype "passive"))
      (node (ref "ENC_1") (pin "16") (pinfunction "VDD5V_16") (pintype "bidirectional"))
      (node (ref "MAIN_1") (pin "1") (pinfunction "1_1") (pintype "passive"))
    )
    (net (code "67") (name "VIN_2") (class "Default")
      (node (ref "C2_1") (pin "1") (pinfunction "1_1") (pintype "passive"))
      (node (ref "ENC_2") (pin "16") (pinfunction "VDD5V_16") (pintype "bidirectional"))
      (node (ref "MAIN_2") (pin "1") (pinfunction "1_1") (pintype "passive"))
    )
    (net (code "68") (name "VIN_3") (class "Default")
      (node (ref "C3_1") (pin "1") (pinfunction "1_1") (pintype "passive"))
      (node (ref "ENC_3") (pin "16") (pinfunction "VDD5V_16") (pintype "bidirectional"))
      (node (ref "MAIN_3") (pin "1") (pinfunction "1_1") (pintype "passive"))
    )
    (net (code "69") (name "unconnected-(ENC_1-NC-Pad5)") (class "Default")
      (node (ref "ENC_1") (pin "5") (pinfunction "NC_5") (pintype "bidirectional"))
    )
    (net (code "70") (name "unconnected-(ENC_1-NC-Pad13)") (class "Default")
      (node (ref "ENC_1") (pin "13") (pinfunction "NC_13") (pintype "bidirectional"))
    )
    (net (code "71") (name "unconnected-(ENC_1-NC-Pad14)") (class "Default")
      (node (ref "ENC_1") (pin "14") (pinfunction "NC_14") (pintype "bidirectional"))
    )
    (net (code "72") (name "unconnected-(ENC_2-NC-Pad5)") (class "Default")
      (node (ref "ENC_2") (pin "5") (pinfunction "NC_5") (pintype "bidirectional"))
    )
    (net (code "73") (name "unconnected-(ENC_2-NC-Pad13)") (class "Default")
      (node (ref "ENC_2") (pin "13") (pinfunction "NC_13") (pintype "bidirectional"))
    )
    (net (code "74") (name "unconnected-(ENC_2-NC-Pad14)") (class "Default")
      (node (ref "ENC_2") (pin "14") (pinfunction "NC_14") (pintype "bidirectional"))
    )
    (net (code "75") (name "unconnected-(ENC_3-NC-Pad5)") (class "Default")
      (node (ref "ENC_3") (pin "5") (pinfunction "NC_5") (pintype "bidirectional"))
    )
    (net (code "76") (name "unconnected-(ENC_3-NC-Pad13)") (class "Default")
      (node (ref "ENC_3") (pin "13") (pinfunction "NC_13") (pintype "bidirectional"))
    )
    (net (code "77") (name "unconnected-(ENC_3-NC-Pad14)") (class "Default")
      (node (ref "ENC_3") (pin "14") (pinfunction "NC_14") (pintype "bidirectional"))
    )
  )
)
